# untitled.net
KiCad netlist of a schematic drawn in EAGLE
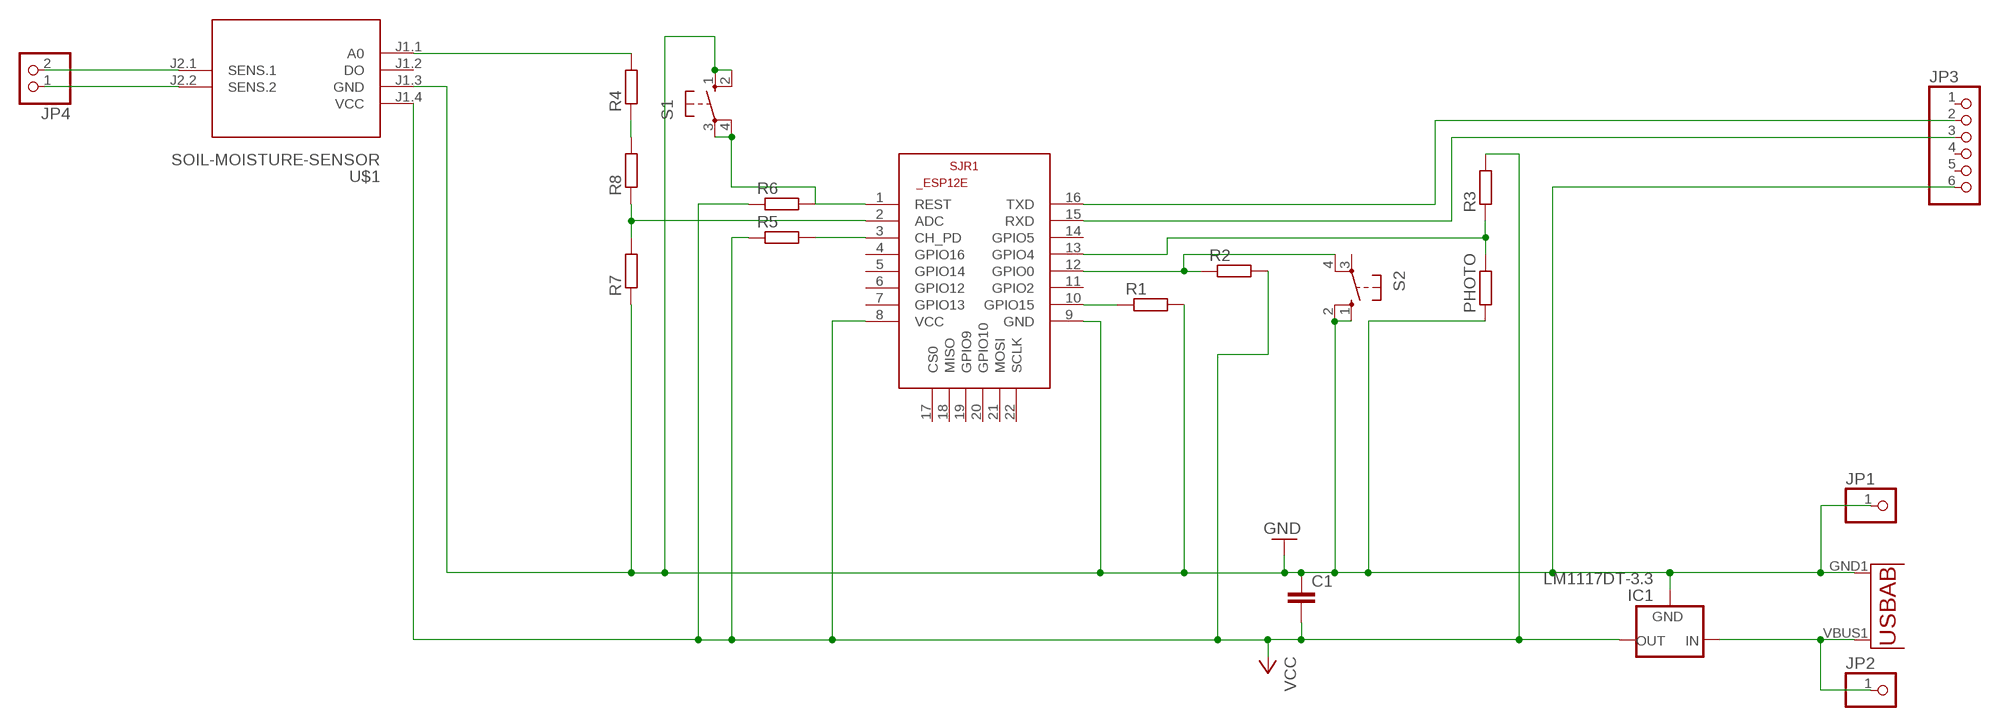
[diagram p0: schematic, sheet 1]

(export (version "E")
  (design (tool "Eeschema 10.0.6"))
  (components
    (comp (ref "C1")
      (value "C-EU050-025X075")
      (footprint "eagle-import:C050-025X075")
      (libsource (lib "eagle-import") (part "C-EU050-025X075"))
    )
    (comp (ref "IC1")
      (value "LM1117DT-3.3")
      (footprint "eagle-import:TO252")
      (fields (field (name "MF") "Texas Instruments"))
      (libsource (lib "eagle-import") (part "LM1117?-DT3.3"))
    )
    (comp (ref "JP1")
      (value "PINHD-1X1")
      (footprint "eagle-import:1X01")
      (libsource (lib "eagle-import") (part "PINHD-1X1"))
    )
    (comp (ref "JP2")
      (value "PINHD-1X1")
      (footprint "eagle-import:1X01")
      (libsource (lib "eagle-import") (part "PINHD-1X1"))
    )
    (comp (ref "JP3")
      (value "PINHD-1X6")
      (footprint "eagle-import:1X06")
      (libsource (lib "eagle-import") (part "PINHD-1X6"))
    )
    (comp (ref "JP4")
      (value "PINHD-1X2")
      (footprint "eagle-import:1X02")
      (libsource (lib "eagle-import") (part "PINHD-1X2"))
    )
    (comp (ref "PHOTO")
      (value "R-EU_0204/5")
      (footprint "eagle-import:0204_5")
      (libsource (lib "eagle-import") (part "R-EU_0204/5"))
    )
    (comp (ref "R1")
      (value "R-EU_0207/10")
      (footprint "eagle-import:0207_10")
      (libsource (lib "eagle-import") (part "R-EU_0207/10"))
    )
    (comp (ref "R2")
      (value "R-EU_0207/10")
      (footprint "eagle-import:0207_10")
      (libsource (lib "eagle-import") (part "R-EU_0207/10"))
    )
    (comp (ref "R3")
      (value "R-EU_0207/10")
      (footprint "eagle-import:0207_10")
      (libsource (lib "eagle-import") (part "R-EU_0207/10"))
    )
    (comp (ref "R4")
      (value "R-EU_0207/10")
      (footprint "eagle-import:0207_10")
      (libsource (lib "eagle-import") (part "R-EU_0207/10"))
    )
    (comp (ref "R5")
      (value "R-EU_0207/10")
      (footprint "eagle-import:0207_10")
      (libsource (lib "eagle-import") (part "R-EU_0207/10"))
    )
    (comp (ref "R6")
      (value "R-EU_0207/10")
      (footprint "eagle-import:0207_10")
      (libsource (lib "eagle-import") (part "R-EU_0207/10"))
    )
    (comp (ref "R7")
      (value "R-EU_0207/10")
      (footprint "eagle-import:0207_10")
      (libsource (lib "eagle-import") (part "R-EU_0207/10"))
    )
    (comp (ref "R8")
      (value "R-EU_0207/10")
      (footprint "eagle-import:0207_10")
      (libsource (lib "eagle-import") (part "R-EU_0207/10"))
    )
    (comp (ref "S1")
      (value "10-XX")
      (footprint "eagle-import:B3F-10XX")
      (fields (field (name "MPN") "B3F-1000"))
      (libsource (lib "eagle-import") (part "10-XX"))
    )
    (comp (ref "S2")
      (value "10-XX")
      (footprint "eagle-import:B3F-10XX")
      (fields (field (name "MPN") "B3F-1000"))
      (libsource (lib "eagle-import") (part "10-XX"))
    )
    (comp (ref "SJR1")
      (value "ESP8266-12EESP12E")
      (footprint "eagle-import:ESP8266-ESP12E")
      (libsource (lib "eagle-import") (part "ESP8266-12EESP12E"))
    )
    (comp (ref "U$1")
      (value "SOIL-MOISTURE-SENSOR")
      (footprint "eagle-import:SOIL-MOISTURE-SENSOR")
      (libsource (lib "eagle-import") (part "SOIL-MOISTURE-SENSOR"))
    )
    (comp (ref "U1")
      (value "USB\"\"")
      (footprint "eagle-import:USB-MICRO-SMD")
      (libsource (lib "eagle-import") (part "USB{dblquote}{dblquote}"))
    )
  )
  (nets
    (net (code "1") (name "GND") (class "Default")
      (node (ref "C1") (pin "1") (pinfunction "1_1") (pintype "passive"))
      (node (ref "IC1") (pin "1") (pinfunction "GND_1") (pintype "input"))
      (node (ref "JP1") (pin "1") (pinfunction "1_1") (pintype "passive"))
      (node (ref "JP3") (pin "6") (pinfunction "6_6") (pintype "passive"))
      (node (ref "PHOTO") (pin "1") (pinfunction "1_1") (pintype "passive"))
      (node (ref "R1") (pin "2") (pinfunction "2_2") (pintype "passive"))
      (node (ref "R7") (pin "1") (pinfunction "1_1") (pintype "passive"))
      (node (ref "S1") (pin "1") (pinfunction "S_1") (pintype "passive"))
      (node (ref "S1") (pin "2") (pinfunction "S1_2") (pintype "passive"))
      (node (ref "S2") (pin "1") (pinfunction "S_1") (pintype "passive"))
      (node (ref "S2") (pin "2") (pinfunction "S1_2") (pintype "passive"))
      (node (ref "SJR1") (pin "9") (pinfunction "GND_9") (pintype "bidirectional"))
      (node (ref "U$1") (pin "J1.3") (pinfunction "GND_J1.3") (pintype "power_in"))
      (node (ref "U1") (pin "GND1") (pinfunction "GND_GND1") (pintype "bidirectional"))
    )
    (net (code "2") (name "Net-(IC1-IN)") (class "Default")
      (node (ref "IC1") (pin "2") (pinfunction "IN_2") (pintype "input"))
      (node (ref "JP2") (pin "1") (pinfunction "1_1") (pintype "passive"))
      (node (ref "U1") (pin "VBUS1") (pinfunction "VBUS_VBUS1") (pintype "bidirectional"))
    )
    (net (code "3") (name "Net-(R4-Pad1)") (class "Default")
      (node (ref "R4") (pin "1") (pinfunction "1_1") (pintype "passive"))
      (node (ref "R8") (pin "2") (pinfunction "2_2") (pintype "passive"))
    )
    (net (code "4") (name "Net-(S1-P)") (class "Default")
      (node (ref "R6") (pin "2") (pinfunction "2_2") (pintype "passive"))
      (node (ref "S1") (pin "3") (pinfunction "P_3") (pintype "passive"))
      (node (ref "S1") (pin "4") (pinfunction "P1_4") (pintype "passive"))
      (node (ref "SJR1") (pin "1") (pinfunction "REST_1") (pintype "bidirectional"))
    )
    (net (code "5") (name "Net-(S2-P1)") (class "Default")
      (node (ref "R2") (pin "1") (pinfunction "1_1") (pintype "passive"))
      (node (ref "S2") (pin "4") (pinfunction "P1_4") (pintype "passive"))
      (node (ref "SJR1") (pin "12") (pinfunction "GPIO0_12") (pintype "bidirectional"))
    )
    (net (code "6") (name "Net-(SJR1-ADC)") (class "Default")
      (node (ref "R7") (pin "2") (pinfunction "2_2") (pintype "passive"))
      (node (ref "R8") (pin "1") (pinfunction "1_1") (pintype "passive"))
      (node (ref "SJR1") (pin "2") (pinfunction "ADC_2") (pintype "bidirectional"))
    )
    (net (code "7") (name "Net-(SJR1-CH_PD)") (class "Default")
      (node (ref "R5") (pin "2") (pinfunction "2_2") (pintype "passive"))
      (node (ref "SJR1") (pin "3") (pinfunction "CH_PD_3") (pintype "bidirectional"))
    )
    (net (code "8") (name "Net-(SJR1-GPIO4)") (class "Default")
      (node (ref "PHOTO") (pin "2") (pinfunction "2_2") (pintype "passive"))
      (node (ref "R3") (pin "1") (pinfunction "1_1") (pintype "passive"))
      (node (ref "SJR1") (pin "13") (pinfunction "GPIO4_13") (pintype "bidirectional"))
    )
    (net (code "9") (name "Net-(SJR1-GPIO15)") (class "Default")
      (node (ref "R1") (pin "1") (pinfunction "1_1") (pintype "passive"))
      (node (ref "SJR1") (pin "10") (pinfunction "GPIO15_10") (pintype "bidirectional"))
    )
    (net (code "10") (name "Net-(SJR1-RXD)") (class "Default")
      (node (ref "JP3") (pin "3") (pinfunction "3_3") (pintype "passive"))
      (node (ref "SJR1") (pin "15") (pinfunction "RXD_15") (pintype "bidirectional"))
    )
    (net (code "11") (name "Net-(SJR1-TXD)") (class "Default")
      (node (ref "JP3") (pin "2") (pinfunction "2_2") (pintype "passive"))
      (node (ref "SJR1") (pin "16") (pinfunction "TXD_16") (pintype "bidirectional"))
    )
    (net (code "12") (name "Net-(U$1-A0)") (class "Default")
      (node (ref "R4") (pin "2") (pinfunction "2_2") (pintype "passive"))
      (node (ref "U$1") (pin "J1.1") (pinfunction "A0_J1.1") (pintype "bidirectional"))
    )
    (net (code "13") (name "Net-(U$1-SENS.1)") (class "Default")
      (node (ref "JP4") (pin "2") (pinfunction "2_2") (pintype "passive"))
      (node (ref "U$1") (pin "J2.1") (pinfunction "SENS.1_J2.1") (pintype "bidirectional"))
    )
    (net (code "14") (name "Net-(U$1-SENS.2)") (class "Default")
      (node (ref "JP4") (pin "1") (pinfunction "1_1") (pintype "passive"))
      (node (ref "U$1") (pin "J2.2") (pinfunction "SENS.2_J2.2") (pintype "bidirectional"))
    )
    (net (code "15") (name "VCC") (class "Default")
      (node (ref "C1") (pin "2") (pinfunction "2_2") (pintype "passive"))
      (node (ref "IC1") (pin "3") (pinfunction "OUT_3") (pintype "passive"))
      (node (ref "R2") (pin "2") (pinfunction "2_2") (pintype "passive"))
      (node (ref "R3") (pin "2") (pinfunction "2_2") (pintype "passive"))
      (node (ref "R5") (pin "1") (pinfunction "1_1") (pintype "passive"))
      (node (ref "R6") (pin "1") (pinfunction "1_1") (pintype "passive"))
      (node (ref "SJR1") (pin "8") (pinfunction "VCC_8") (pintype "bidirectional"))
      (node (ref "U$1") (pin "J1.4") (pinfunction "VCC_J1.4") (pintype "power_in"))
    )
    (net (code "16") (name "unconnected-(JP3-Pad1)") (class "Default")
      (node (ref "JP3") (pin "1") (pinfunction "1_1") (pintype "passive"))
    )
    (net (code "17") (name "unconnected-(JP3-Pad4)") (class "Default")
      (node (ref "JP3") (pin "4") (pinfunction "4_4") (pintype "passive"))
    )
    (net (code "18") (name "unconnected-(JP3-Pad5)") (class "Default")
      (node (ref "JP3") (pin "5") (pinfunction "5_5") (pintype "passive"))
    )
    (net (code "19") (name "unconnected-(S2-P-Pad3)") (class "Default")
      (node (ref "S2") (pin "3") (pinfunction "P_3") (pintype "passive"))
    )
    (net (code "20") (name "unconnected-(SJR1-CS0-Pad17)") (class "Default")
      (node (ref "SJR1") (pin "17") (pinfunction "CS0_17") (pintype "bidirectional"))
    )
    (net (code "21") (name "unconnected-(SJR1-GPIO2-Pad11)") (class "Default")
      (node (ref "SJR1") (pin "11") (pinfunction "GPIO2_11") (pintype "bidirectional"))
    )
    (net (code "22") (name "unconnected-(SJR1-GPIO5-Pad14)") (class "Default")
      (node (ref "SJR1") (pin "14") (pinfunction "GPIO5_14") (pintype "bidirectional"))
    )
    (net (code "23") (name "unconnected-(SJR1-GPIO9-Pad19)") (class "Default")
      (node (ref "SJR1") (pin "19") (pinfunction "GPIO9_19") (pintype "bidirectional"))
    )
    (net (code "24") (name "unconnected-(SJR1-GPIO10-Pad20)") (class "Default")
      (node (ref "SJR1") (pin "20") (pinfunction "GPIO10_20") (pintype "bidirectional"))
    )
    (net (code "25") (name "unconnected-(SJR1-GPIO12-Pad6)") (class "Default")
      (node (ref "SJR1") (pin "6") (pinfunction "GPIO12_6") (pintype "bidirectional"))
    )
    (net (code "26") (name "unconnected-(SJR1-GPIO13-Pad7)") (class "Default")
      (node (ref "SJR1") (pin "7") (pinfunction "GPIO13_7") (pintype "bidirectional"))
    )
    (net (code "27") (name "unconnected-(SJR1-GPIO14-Pad5)") (class "Default")
      (node (ref "SJR1") (pin "5") (pinfunction "GPIO14_5") (pintype "bidirectional"))
    )
    (net (code "28") (name "unconnected-(SJR1-GPIO16-Pad4)") (class "Default")
      (node (ref "SJR1") (pin "4") (pinfunction "GPIO16_4") (pintype "bidirectional"))
    )
    (net (code "29") (name "unconnected-(SJR1-MISO-Pad18)") (class "Default")
      (node (ref "SJR1") (pin "18") (pinfunction "MISO_18") (pintype "bidirectional"))
    )
    (net (code "30") (name "unconnected-(SJR1-MOSI-Pad21)") (class "Default")
      (node (ref "SJR1") (pin "21") (pinfunction "MOSI_21") (pintype "bidirectional"))
    )
    (net (code "31") (name "unconnected-(SJR1-SCLK-Pad22)") (class "Default")
      (node (ref "SJR1") (pin "22") (pinfunction "SCLK_22") (pintype "bidirectional"))
    )
    (net (code "32") (name "unconnected-(U$1-DO-PadJ1.2)") (class "Default")
      (node (ref "U$1") (pin "J1.2") (pinfunction "DO_J1.2") (pintype "output"))
    )
  )
)
